# ESP32.net
KiCad netlist of a schematic drawn in EasyEDA Pro
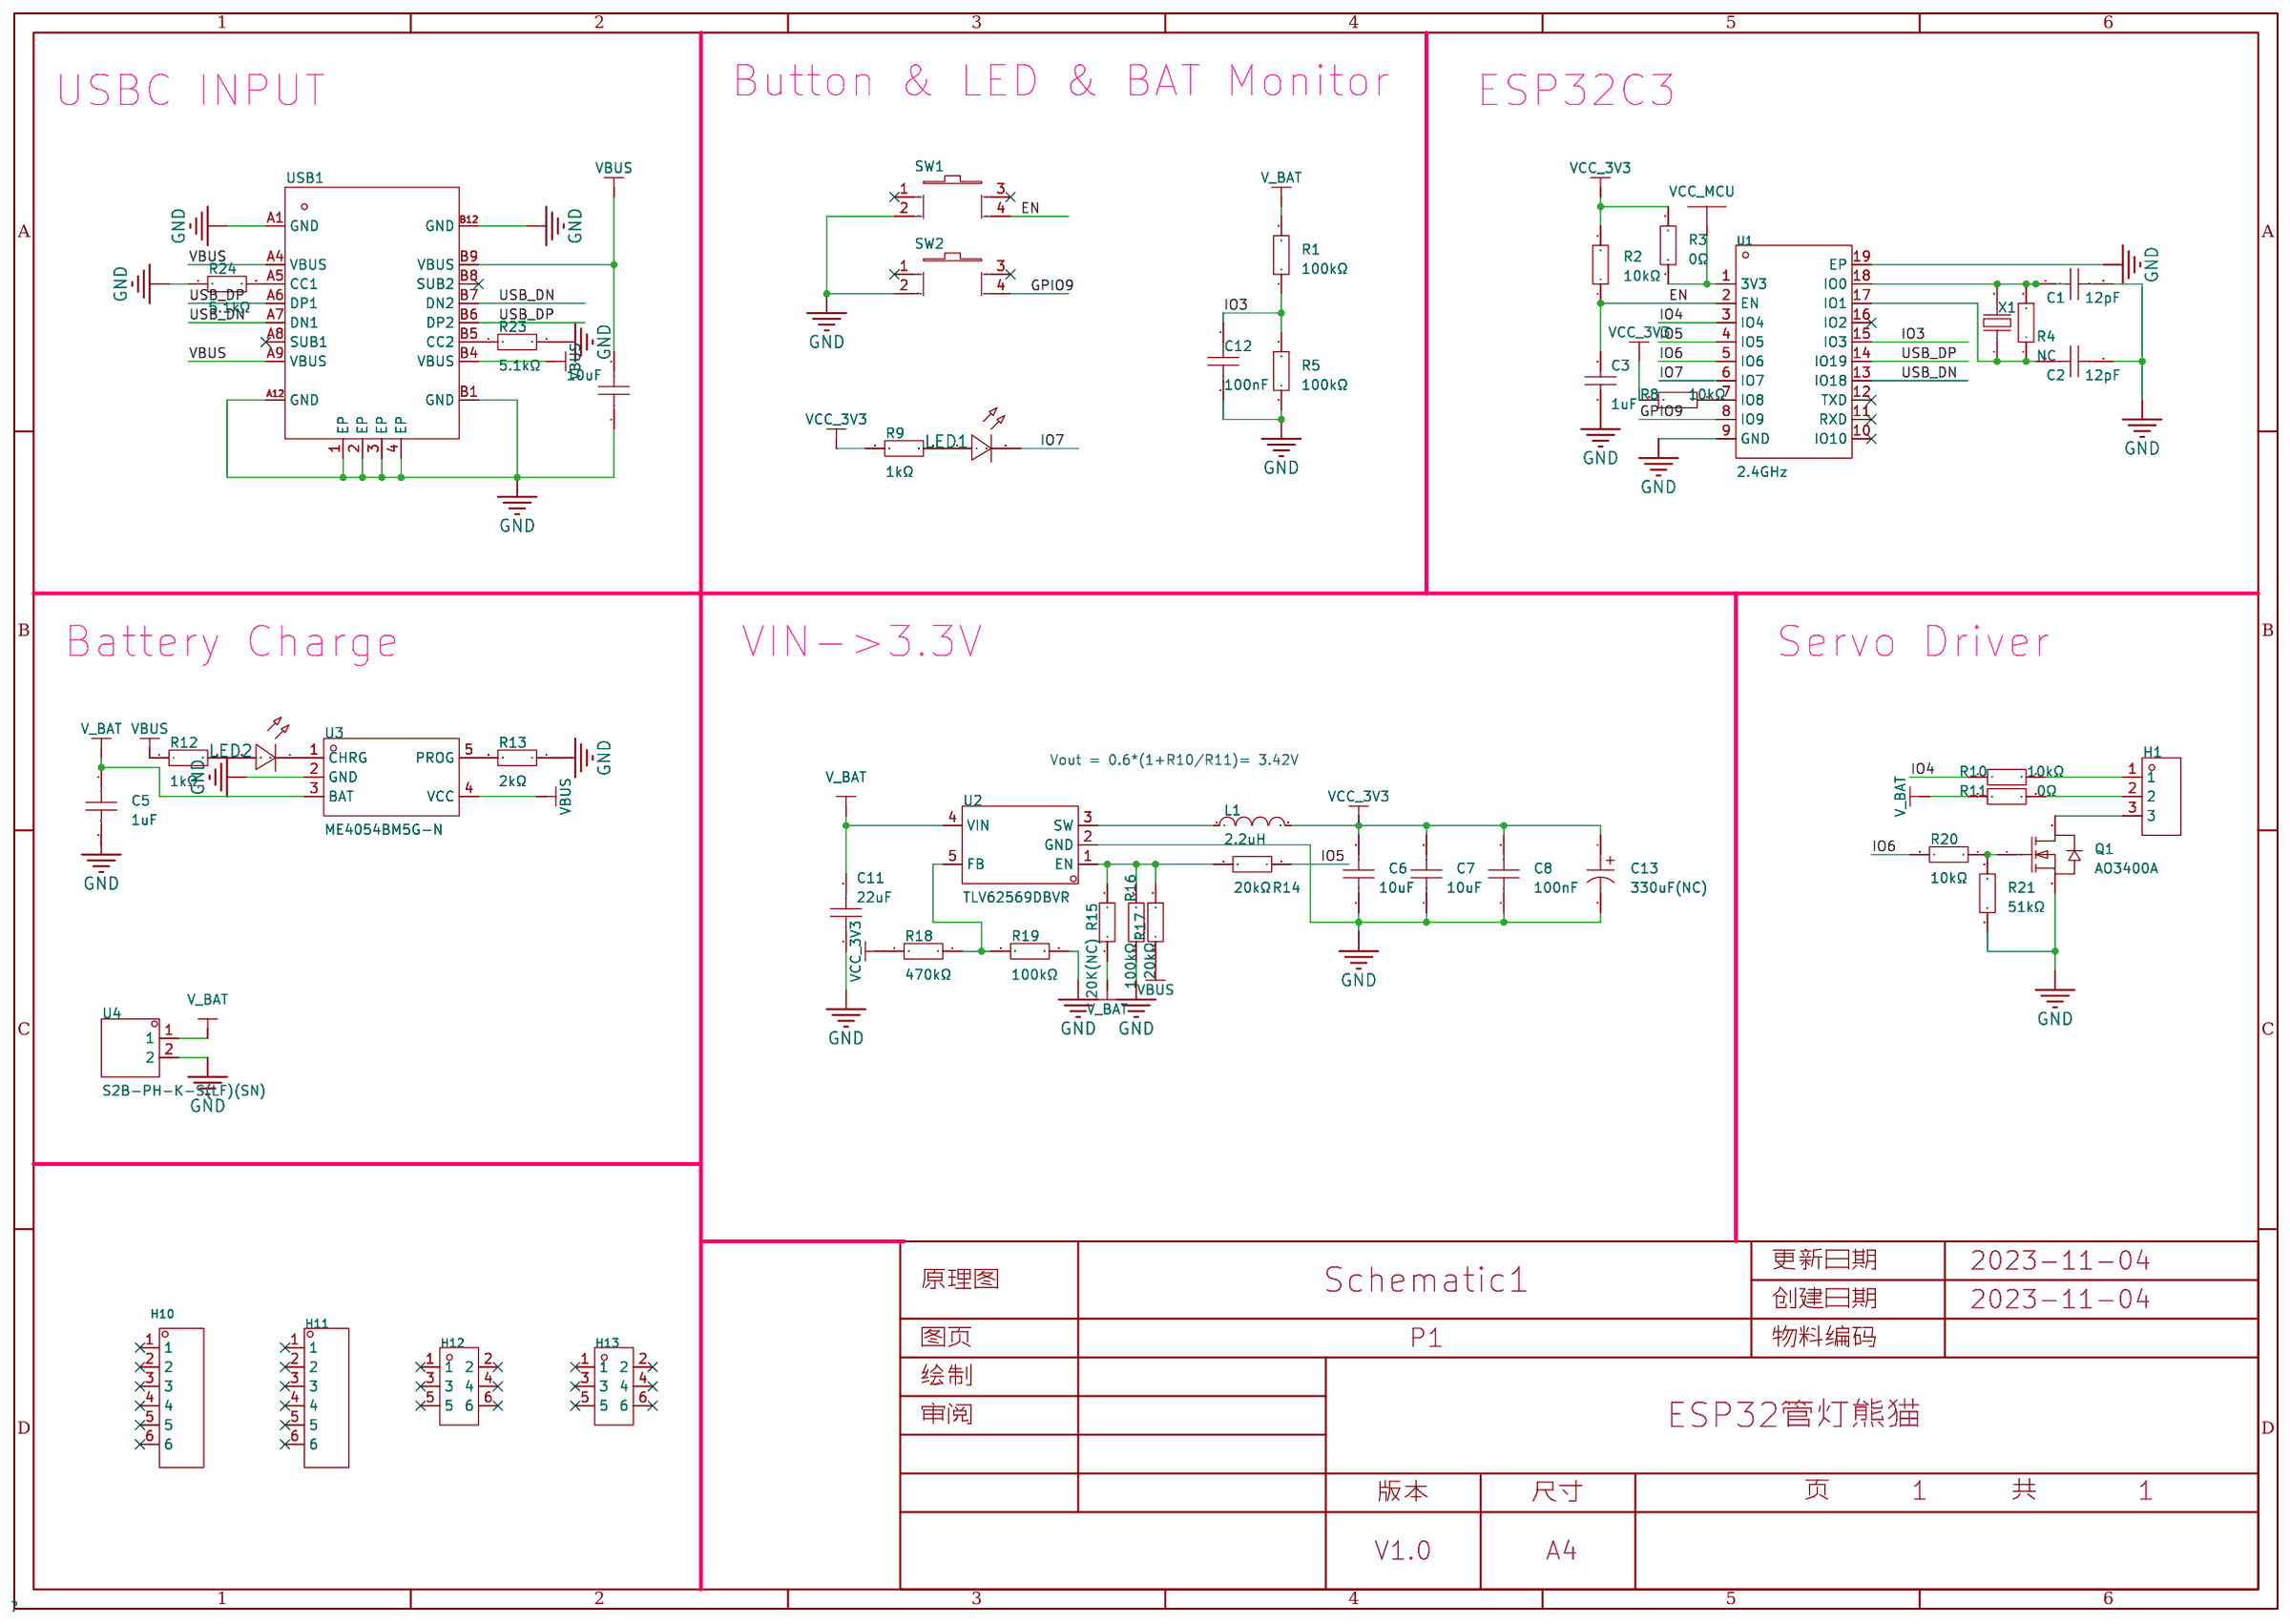
[diagram p0: schematic sheet]

(export (version "E")
  (design (tool "Eeschema 10.0.6"))
  (components
    (comp (ref "C1")
      (value "12pF")
      (footprint "easyedapro:C0603")
      (fields
        (field (name "Manufacturer Part") "CL10C120JB8NNNC")
        (field (name "Manufacturer") "SAMSUNG(三星)")
      )
      (libsource (lib "easyedapro") (part "CapAcitance"))
    )
    (comp (ref "C2")
      (value "12pF")
      (footprint "easyedapro:C0603")
      (fields
        (field (name "Manufacturer Part") "CL10C120JB8NNNC")
        (field (name "Manufacturer") "SAMSUNG(三星)")
      )
      (libsource (lib "easyedapro") (part "CapAcitance"))
    )
    (comp (ref "C3")
      (value "1uF")
      (footprint "easyedapro:C0603")
      (description "容值:1uF;精度:±10%;额定电压:25V;温度系数:X5R;")
      (fields
        (field (name "Manufacturer Part") "CL10A105KA8NNNC")
        (field (name "Manufacturer") "SAMSUNG(三星)")
      )
      (libsource (lib "easyedapro") (part "CL10A105KA8NNNC"))
    )
    (comp (ref "C4")
      (value "10uF")
      (footprint "easyedapro:C0603")
      (description "容值:10uF;精度:±20%;额定电压:10V;温度系数:X5R;")
      (fields
        (field (name "Manufacturer Part") "CL10A106MP8NNNC")
        (field (name "Manufacturer") "SAMSUNG(三星)")
      )
      (libsource (lib "easyedapro") (part "CL10A106MP8NNNC"))
    )
    (comp (ref "C5")
      (value "1uF")
      (footprint "easyedapro:C0603")
      (fields
        (field (name "Manufacturer Part") "CL10A105KB8NNNC")
        (field (name "Manufacturer") "SAMSUNG(三星)")
      )
      (libsource (lib "easyedapro") (part "CapAcitance"))
    )
    (comp (ref "C6")
      (value "10uF")
      (footprint "easyedapro:C0603")
      (fields
        (field (name "Manufacturer Part") "CL10A106KP8NNNC")
        (field (name "Manufacturer") "SAMSUNG(三星)")
      )
      (libsource (lib "easyedapro") (part "CapAcitance"))
    )
    (comp (ref "C7")
      (value "10uF")
      (footprint "easyedapro:C0603")
      (fields
        (field (name "Manufacturer Part") "CL10A106KP8NNNC")
        (field (name "Manufacturer") "SAMSUNG(三星)")
      )
      (libsource (lib "easyedapro") (part "CapAcitance"))
    )
    (comp (ref "C8")
      (value "100nF")
      (footprint "easyedapro:C0603")
      (fields
        (field (name "Manufacturer Part") "CC0603KRX7R9BB104")
        (field (name "Manufacturer") "YAGEO(国巨)")
      )
      (libsource (lib "easyedapro") (part "CapAcitance"))
    )
    (comp (ref "C11")
      (value "22uF")
      (footprint "easyedapro:C0603")
      (fields
        (field (name "Manufacturer Part") "CL10A226MQ8NRNC")
        (field (name "Manufacturer") "SAMSUNG(三星)")
      )
      (libsource (lib "easyedapro") (part "CapAcitance"))
    )
    (comp (ref "C12")
      (value "100nF")
      (footprint "easyedapro:C0603")
      (fields
        (field (name "Manufacturer Part") "CC0603KRX7R9BB104")
        (field (name "Manufacturer") "YAGEO(国巨)")
      )
      (libsource (lib "easyedapro") (part "CapAcitance"))
    )
    (comp (ref "C13")
      (value "330uF(NC)")
      (footprint "easyedapro:CAP-SMD_BD6.3-L6.6-W6.6-LS7.4-FD")
      (description "容值:330uF;精度:±20%;额定电压:6.3V;")
      (fields (field (name "Manufacturer Part") "RVT0J331M0605") (field (name "Manufacturer") "ROQANG(容强)"))
      (libsource (lib "easyedapro") (part "RVT0J331M0605"))
    )
    (comp (ref "H1")
      (value "~")
      (footprint "easyedapro:HDR-TH_3P-P2.54-V-M")
      (libsource (lib "easyedapro") (part "PZ254V-11-03P_C2937625"))
    )
    (comp (ref "H10")
      (value "B-2200S06P-A120")
      (footprint "easyedapro:HDR-TH_6P-P2.54-V-F")
      (description "排数:单排;总孔位数:6;间距:2.54mm;插孔结构:1x6P;行距:-;安装类型:直插;塑高:-;触头材质:黄铜;触头镀层:-;")
      (fields (field (name "Manufacturer") "Ckmtw(灿科盟)"))
      (libsource (lib "easyedapro") (part "220S-1*6P H=8.5MM Ytype Gold-plated"))
    )
    (comp (ref "H11")
      (value "B-2200S06P-A120")
      (footprint "easyedapro:HDR-TH_6P-P2.54-V-F")
      (description "排数:单排;总孔位数:6;间距:2.54mm;插孔结构:1x6P;行距:-;安装类型:直插;塑高:-;触头材质:黄铜;触头镀层:-;")
      (fields (field (name "Manufacturer") "Ckmtw(灿科盟)"))
      (libsource (lib "easyedapro") (part "220S-1*6P H=8.5MM Ytype Gold-plated"))
    )
    (comp (ref "H12")
      (value "X6511WVS-06H-C60D48R2")
      (footprint "easyedapro:HDR-SMD_6P-P2.54-V-M-LS4.8_R2")
      (fields (field (name "Manufacturer") "XKB Connectivity(中国星坤)"))
      (libsource (lib "easyedapro") (part "X6511WVS-06H-C60D48R2"))
    )
    (comp (ref "H13")
      (value "X6511WVS-06H-C60D48R2")
      (footprint "easyedapro:HDR-SMD_6P-P2.54-V-M-LS4.8_R2")
      (fields (field (name "Manufacturer") "XKB Connectivity(中国星坤)"))
      (libsource (lib "easyedapro") (part "X6511WVS-06H-C60D48R2"))
    )
    (comp (ref "L1")
      (value "2.2uH")
      (footprint "easyedapro:IND-SMD_L2.5-W2.0_SWPA2520")
      (description "电感值:2.2uH;精度:±20%;额定电流:1.25A;直流电阻(DCR):216mΩ;")
      (fields
        (field (name "Manufacturer Part") "SWPA252012S2R2MT")
        (field (name "Manufacturer") "Sunlord(顺络)")
      )
      (libsource (lib "easyedapro") (part "SWPA252012S-2R2MT"))
    )
    (comp (ref "LED1")
      (value "19-217/BHC-ZL1M2RY/3T")
      (description "发光颜色:蓝灯;二极管配置:-;主波长:465nm~475nm;色温:-;功率:110mW;安装方式:-;")
      (fields (field (name "Manufacturer") "EVERLIGHT(亿光)"))
      (libsource (lib "easyedapro") (part "LED_R"))
    )
    (comp (ref "LED2")
      (value "19-217/BHC-ZL1M2RY/3T")
      (description "发光颜色:蓝灯;二极管配置:-;主波长:465nm~475nm;色温:-;功率:110mW;安装方式:-;")
      (fields (field (name "Manufacturer") "EVERLIGHT(亿光)"))
      (libsource (lib "easyedapro") (part "LED_R"))
    )
    (comp (ref "Q1")
      (value "AO3400A")
      (footprint "easyedapro:SOT-23-3_L2.9-W1.6-P1.90-LS2.8-BR")
      (description "类型:N沟道;漏源电压(Vdss):30V;连续漏极电流(Id):5.7A;功率(Pd):1.4W;导通电阻(RDS(on)@Vgs,Id):26.5mΩ@10V,5.7A;")
      (fields (field (name "Manufacturer") "AOS"))
      (libsource (lib "easyedapro") (part "AO3400A"))
    )
    (comp (ref "R1")
      (value "100kΩ")
      (footprint "easyedapro:R0603")
      (fields
        (field (name "Manufacturer Part") "0603WAF1003T5E")
        (field (name "Manufacturer") "UNI-ROYAL(厚声)")
      )
      (libsource (lib "easyedapro") (part "电阻"))
    )
    (comp (ref "R2")
      (value "10kΩ")
      (footprint "easyedapro:R0402")
      (fields
        (field (name "Manufacturer Part") "0603WAF1002T5E")
        (field (name "Manufacturer") "UNI-ROYAL(厚声)")
      )
      (libsource (lib "easyedapro") (part "电阻"))
    )
    (comp (ref "R3")
      (value "0Ω")
      (footprint "easyedapro:R0603")
      (fields
        (field (name "Manufacturer Part") "0603WAF0000T5E")
        (field (name "Manufacturer") "UNI-ROYAL(厚声)")
      )
      (libsource (lib "easyedapro") (part "电阻"))
    )
    (comp (ref "R4") (value "NC") (footprint "easyedapro:R0603") (libsource (lib "easyedapro") (part "电阻")))
    (comp (ref "R5")
      (value "100kΩ")
      (footprint "easyedapro:R0603")
      (fields
        (field (name "Manufacturer Part") "0603WAF1003T5E")
        (field (name "Manufacturer") "UNI-ROYAL(厚声)")
      )
      (libsource (lib "easyedapro") (part "电阻"))
    )
    (comp (ref "R8")
      (value "10kΩ")
      (footprint "easyedapro:R0402")
      (fields
        (field (name "Manufacturer Part") "0603WAF1002T5E")
        (field (name "Manufacturer") "UNI-ROYAL(厚声)")
      )
      (libsource (lib "easyedapro") (part "电阻"))
    )
    (comp (ref "R9")
      (value "1kΩ")
      (footprint "easyedapro:R0402")
      (fields
        (field (name "Manufacturer Part") "0603WAF1001T5E")
        (field (name "Manufacturer") "UNI-ROYAL(厚声)")
      )
      (libsource (lib "easyedapro") (part "电阻"))
    )
    (comp (ref "R10")
      (value "10kΩ")
      (footprint "easyedapro:R0603")
      (fields
        (field (name "Manufacturer Part") "0603WAF1002T5E")
        (field (name "Manufacturer") "UNI-ROYAL(厚声)")
      )
      (libsource (lib "easyedapro") (part "电阻"))
    )
    (comp (ref "R11")
      (value "0Ω")
      (footprint "easyedapro:R0603")
      (fields
        (field (name "Manufacturer Part") "0603WAF0000T5E")
        (field (name "Manufacturer") "UNI-ROYAL(厚声)")
      )
      (libsource (lib "easyedapro") (part "电阻"))
    )
    (comp (ref "R12")
      (value "1kΩ")
      (footprint "easyedapro:R0402")
      (fields
        (field (name "Manufacturer Part") "0603WAF1001T5E")
        (field (name "Manufacturer") "UNI-ROYAL(厚声)")
      )
      (libsource (lib "easyedapro") (part "电阻"))
    )
    (comp (ref "R13")
      (value "2kΩ")
      (footprint "easyedapro:R0402")
      (fields
        (field (name "Manufacturer Part") "0603WAF2001T5E")
        (field (name "Manufacturer") "UNI-ROYAL(厚声)")
      )
      (libsource (lib "easyedapro") (part "电阻"))
    )
    (comp (ref "R14")
      (value "20kΩ")
      (footprint "easyedapro:R0402")
      (fields
        (field (name "Manufacturer Part") "0603WAF2002T5E")
        (field (name "Manufacturer") "UNI-ROYAL(厚声)")
      )
      (libsource (lib "easyedapro") (part "电阻"))
    )
    (comp (ref "R15")
      (value "20K(NC)")
      (footprint "easyedapro:R0402")
      (libsource (lib "easyedapro") (part "电阻"))
    )
    (comp (ref "R16")
      (value "100kΩ")
      (footprint "easyedapro:R0402")
      (fields
        (field (name "Manufacturer Part") "0603WAF1003T5E")
        (field (name "Manufacturer") "UNI-ROYAL(厚声)")
      )
      (libsource (lib "easyedapro") (part "电阻"))
    )
    (comp (ref "R17")
      (value "20kΩ")
      (footprint "easyedapro:R0402")
      (fields
        (field (name "Manufacturer Part") "0603WAF2002T5E")
        (field (name "Manufacturer") "UNI-ROYAL(厚声)")
      )
      (libsource (lib "easyedapro") (part "电阻"))
    )
    (comp (ref "R18")
      (value "470kΩ")
      (footprint "easyedapro:R0402")
      (fields
        (field (name "Manufacturer Part") "0603WAF4703T5E")
        (field (name "Manufacturer") "UNI-ROYAL(厚声)")
      )
      (libsource (lib "easyedapro") (part "电阻"))
    )
    (comp (ref "R19")
      (value "100kΩ")
      (footprint "easyedapro:R0402")
      (fields
        (field (name "Manufacturer Part") "0603WAF1003T5E")
        (field (name "Manufacturer") "UNI-ROYAL(厚声)")
      )
      (libsource (lib "easyedapro") (part "电阻"))
    )
    (comp (ref "R20")
      (value "10kΩ")
      (footprint "easyedapro:R0402")
      (fields
        (field (name "Manufacturer Part") "0603WAF1002T5E")
        (field (name "Manufacturer") "UNI-ROYAL(厚声)")
      )
      (libsource (lib "easyedapro") (part "电阻"))
    )
    (comp (ref "R21")
      (value "51kΩ")
      (footprint "easyedapro:R0402")
      (fields
        (field (name "Manufacturer Part") "0603WAF5102T5E")
        (field (name "Manufacturer") "UNI-ROYAL(厚声)")
      )
      (libsource (lib "easyedapro") (part "电阻"))
    )
    (comp (ref "R23")
      (value "5.1kΩ")
      (footprint "easyedapro:R0603")
      (description "电阻类型:厚膜电阻;阻值:5.1kΩ;精度:±1%;功率:100mW;")
      (fields
        (field (name "Manufacturer Part") "0603WAF5101T5E")
        (field (name "Manufacturer") "UNI-ROYAL(厚声)")
      )
      (libsource (lib "easyedapro") (part "0603WAF5101T5E"))
    )
    (comp (ref "R24")
      (value "5.1kΩ")
      (footprint "easyedapro:R0603")
      (description "电阻类型:厚膜电阻;阻值:5.1kΩ;精度:±1%;功率:100mW;")
      (fields
        (field (name "Manufacturer Part") "0603WAF5101T5E")
        (field (name "Manufacturer") "UNI-ROYAL(厚声)")
      )
      (libsource (lib "easyedapro") (part "0603WAF5101T5E"))
    )
    (comp (ref "SW1")
      (value "~")
      (footprint "easyedapro:SW-SMD_4P_PTS810SJM250SMTRLFS")
      (description "触点电流:50mA;额定电压(DC):16V;电路结构:单刀单掷;安装方式:-;按钮形状:圆形按钮;带灯:-;开关长度:4.2mm;开关宽度:3.2mm;开关高度:2.5mm;")
      (fields
        (field (name "Manufacturer Part") "PTS810SJS250SMTRLFS")
        (field (name "Manufacturer") "C&amp;K")
      )
      (libsource (lib "easyedapro") (part "PTS810SJS250SMTRLFS"))
    )
    (comp (ref "SW2")
      (value "~")
      (footprint "easyedapro:SW-SMD_4P_PTS810SJM250SMTRLFS")
      (description "触点电流:50mA;额定电压(DC):16V;电路结构:单刀单掷;安装方式:-;按钮形状:圆形按钮;带灯:-;开关长度:4.2mm;开关宽度:3.2mm;开关高度:2.5mm;")
      (fields
        (field (name "Manufacturer Part") "PTS810SJS250SMTRLFS")
        (field (name "Manufacturer") "C&amp;K")
      )
      (libsource (lib "easyedapro") (part "PTS810SJS250SMTRLFS"))
    )
    (comp (ref "U1")
      (value "2.4GHz")
      (footprint "easyedapro:BULETM-SMD_ESPRESSIF_ESP32-C3-WROOM-02-N4-4MB")
      (description "频率:2.4GHz;发射功率:20.5dBm;核心处理器:ESP32-C3;")
      (fields
        (field (name "Manufacturer Part") "ESP32-C3-WROOM-02-N4")
        (field (name "Manufacturer") "ESPRESSIF(乐鑫)")
      )
      (libsource (lib "easyedapro") (part "ESP32-C3-WROOM-02-N4(4MB)"))
    )
    (comp (ref "U2")
      (value "TLV62569DBVR")
      (footprint "easyedapro:SOT-23-5_L3.0-W1.7-P0.95-LS2.8-BR")
      (description "功能类型:降压型;输出类型:可调;输入电压:2.5V~5.5V;输出电压:600mV~5.5V;输出电流(最大值):2A;")
      (fields (field (name "Manufacturer") "TI(德州仪器)"))
      (libsource (lib "easyedapro") (part "TLV62569DBVR"))
    )
    (comp (ref "U3")
      (value "ME4054BM5G-N")
      (footprint "easyedapro:TSOT-23-5_L2.9-W1.6-P0.95-LS2.8-BL")
      (fields (field (name "Manufacturer") "MICRONE(南京微盟)"))
      (libsource (lib "easyedapro") (part "ME4054BM5G-N"))
    )
    (comp (ref "U4")
      (value "S2B-PH-K-S(LF)(SN)")
      (footprint "easyedapro:CONN-TH_S2B-PH-K-S-LF-SN")
      (description "参考系列:PH;间距:2mm;插针结构:1x2P;排数:1;每排PIN数:2;行距:-;安装方式:-;触头材质:黄铜;")
      (fields (field (name "Manufacturer") "JST"))
      (libsource (lib "easyedapro") (part "S2B-PH-K-S(LF)(SN)"))
    )
    (comp (ref "USB1")
      (value "KH-TYPE-C-16P")
      (fields (field (name "Manufacturer") "kinghelm(金航标)"))
      (libsource (lib "easyedapro") (part "KH-TYPE-C-16P"))
    )
    (comp (ref "X1")
      (value "32.768kHz")
      (footprint "easyedapro:FC-135R_L3.2-W1.5")
      (description "频率:32.768kHz;频率公差:±20ppm;负载电容:12.5pF;")
      (fields (field (name "Manufacturer Part") "Q13FC1350000400") (field (name "Manufacturer") "EPSON(爱普生)"))
      (libsource (lib "easyedapro") (part "Q13FC1350000400"))
    )
  )
  (nets
    (net (code "1") (name "/EN") (class "Default")
      (node (ref "C3") (pin "2") (pinfunction "2_2") (pintype "input"))
      (node (ref "R2") (pin "1") (pinfunction "1_1") (pintype "input"))
      (node (ref "SW1") (pin "4") (pinfunction "4_4") (pintype "input"))
      (node (ref "U1") (pin "2") (pinfunction "EN_2") (pintype "input"))
    )
    (net (code "2") (name "/GPIO9") (class "Default")
      (node (ref "SW2") (pin "4") (pinfunction "4_4") (pintype "input"))
      (node (ref "U1") (pin "8") (pinfunction "IO9_8") (pintype "input"))
    )
    (net (code "3") (name "/IO3") (class "Default")
      (node (ref "C12") (pin "2") (pinfunction "2_2") (pintype "input"))
      (node (ref "R1") (pin "1") (pinfunction "1_1") (pintype "input"))
      (node (ref "R5") (pin "2") (pinfunction "2_2") (pintype "input"))
      (node (ref "U1") (pin "15") (pinfunction "IO3_15") (pintype "input"))
    )
    (net (code "4") (name "/IO4") (class "Default")
      (node (ref "R10") (pin "1") (pinfunction "1_1") (pintype "input"))
      (node (ref "U1") (pin "3") (pinfunction "IO4_3") (pintype "input"))
    )
    (net (code "5") (name "/IO5") (class "Default")
      (node (ref "R14") (pin "1") (pinfunction "1_1") (pintype "input"))
      (node (ref "U1") (pin "4") (pinfunction "IO5_4") (pintype "input"))
    )
    (net (code "6") (name "/IO6") (class "Default")
      (node (ref "R20") (pin "2") (pinfunction "2_2") (pintype "input"))
      (node (ref "U1") (pin "5") (pinfunction "IO6_5") (pintype "input"))
    )
    (net (code "7") (name "/IO7") (class "Default")
      (node (ref "LED1") (pin "1") (pinfunction "C_1") (pintype "input"))
      (node (ref "U1") (pin "6") (pinfunction "IO7_6") (pintype "input"))
    )
    (net (code "8") (name "/USB_DN") (class "Default")
      (node (ref "U1") (pin "13") (pinfunction "IO18_13") (pintype "input"))
      (node (ref "USB1") (pin "A7") (pinfunction "DN1_A7") (pintype "input"))
      (node (ref "USB1") (pin "B7") (pinfunction "DN2_B7") (pintype "input"))
    )
    (net (code "9") (name "/USB_DP") (class "Default")
      (node (ref "U1") (pin "14") (pinfunction "IO19_14") (pintype "input"))
      (node (ref "USB1") (pin "A6") (pinfunction "DP1_A6") (pintype "input"))
      (node (ref "USB1") (pin "B6") (pinfunction "DP2_B6") (pintype "input"))
    )
    (net (code "10") (name "GND") (class "Default")
      (node (ref "C1") (pin "2") (pinfunction "2_2") (pintype "input"))
      (node (ref "C11") (pin "1") (pinfunction "1_1") (pintype "input"))
      (node (ref "C12") (pin "1") (pinfunction "1_1") (pintype "input"))
      (node (ref "C13") (pin "2") (pinfunction "2_2") (pintype "input"))
      (node (ref "C2") (pin "2") (pinfunction "2_2") (pintype "input"))
      (node (ref "C3") (pin "1") (pinfunction "1_1") (pintype "input"))
      (node (ref "C4") (pin "1") (pinfunction "1_1") (pintype "input"))
      (node (ref "C5") (pin "2") (pinfunction "2_2") (pintype "input"))
      (node (ref "C6") (pin "1") (pinfunction "1_1") (pintype "input"))
      (node (ref "C7") (pin "1") (pinfunction "1_1") (pintype "input"))
      (node (ref "C8") (pin "1") (pinfunction "1_1") (pintype "input"))
      (node (ref "Q1") (pin "2") (pinfunction "S_2") (pintype "input"))
      (node (ref "R13") (pin "1") (pinfunction "1_1") (pintype "input"))
      (node (ref "R16") (pin "1") (pinfunction "1_1") (pintype "input"))
      (node (ref "R19") (pin "1") (pinfunction "1_1") (pintype "input"))
      (node (ref "R21") (pin "1") (pinfunction "1_1") (pintype "input"))
      (node (ref "R23") (pin "2") (pinfunction "2_2") (pintype "input"))
      (node (ref "R24") (pin "1") (pinfunction "1_1") (pintype "input"))
      (node (ref "R5") (pin "1") (pinfunction "1_1") (pintype "input"))
      (node (ref "SW1") (pin "2") (pinfunction "2_2") (pintype "input"))
      (node (ref "SW2") (pin "2") (pinfunction "2_2") (pintype "input"))
      (node (ref "U1") (pin "19") (pinfunction "EP_19") (pintype "input"))
      (node (ref "U1") (pin "9") (pinfunction "GND_9") (pintype "input"))
      (node (ref "U2") (pin "2") (pinfunction "GND_2") (pintype "input"))
      (node (ref "U3") (pin "2") (pinfunction "GND_2") (pintype "input"))
      (node (ref "U4") (pin "2") (pinfunction "2_2") (pintype "input"))
      (node (ref "USB1") (pin "1") (pinfunction "EP_1") (pintype "input"))
      (node (ref "USB1") (pin "2") (pinfunction "EP_2") (pintype "input"))
      (node (ref "USB1") (pin "3") (pinfunction "EP_3") (pintype "input"))
      (node (ref "USB1") (pin "4") (pinfunction "EP_4") (pintype "input"))
      (node (ref "USB1") (pin "A1") (pinfunction "GND_A1") (pintype "input"))
      (node (ref "USB1") (pin "A12") (pinfunction "GND_A12") (pintype "input"))
      (node (ref "USB1") (pin "B1") (pinfunction "GND_B1") (pintype "input"))
      (node (ref "USB1") (pin "B12") (pinfunction "GND_B12") (pintype "input"))
    )
    (net (code "11") (name "Net-(H1-Pad1)") (class "Default")
      (node (ref "H1") (pin "1") (pinfunction "1_1") (pintype "input"))
      (node (ref "R10") (pin "2") (pinfunction "2_2") (pintype "input"))
    )
    (net (code "12") (name "Net-(H1-Pad2)") (class "Default")
      (node (ref "H1") (pin "2") (pinfunction "2_2") (pintype "input"))
      (node (ref "R11") (pin "2") (pinfunction "2_2") (pintype "input"))
    )
    (net (code "13") (name "Net-(LED1-A)") (class "Default")
      (node (ref "LED1") (pin "2") (pinfunction "A_2") (pintype "input"))
      (node (ref "R9") (pin "2") (pinfunction "2_2") (pintype "input"))
    )
    (net (code "14") (name "Net-(LED2-A)") (class "Default")
      (node (ref "LED2") (pin "2") (pinfunction "A_2") (pintype "input"))
      (node (ref "R12") (pin "2") (pinfunction "2_2") (pintype "input"))
    )
    (net (code "15") (name "Net-(LED2-C)") (class "Default")
      (node (ref "LED2") (pin "1") (pinfunction "C_1") (pintype "input"))
      (node (ref "U3") (pin "1") (pinfunction "CHRG_1") (pintype "input"))
    )
    (net (code "16") (name "Net-(Q1-D)") (class "Default")
      (node (ref "H1") (pin "3") (pinfunction "3_3") (pintype "input"))
      (node (ref "Q1") (pin "3") (pinfunction "D_3") (pintype "input"))
    )
    (net (code "17") (name "Net-(Q1-G)") (class "Default")
      (node (ref "Q1") (pin "1") (pinfunction "G_1") (pintype "input"))
      (node (ref "R20") (pin "1") (pinfunction "1_1") (pintype "input"))
      (node (ref "R21") (pin "2") (pinfunction "2_2") (pintype "input"))
    )
    (net (code "18") (name "Net-(U1-IO0)") (class "Default")
      (node (ref "C1") (pin "1") (pinfunction "1_1") (pintype "input"))
      (node (ref "R4") (pin "2") (pinfunction "2_2") (pintype "input"))
      (node (ref "U1") (pin "18") (pinfunction "IO0_18") (pintype "input"))
      (node (ref "X1") (pin "2") (pinfunction "2_2") (pintype "input"))
    )
    (net (code "19") (name "Net-(U1-IO1)") (class "Default")
      (node (ref "C2") (pin "1") (pinfunction "1_1") (pintype "input"))
      (node (ref "R4") (pin "1") (pinfunction "1_1") (pintype "input"))
      (node (ref "U1") (pin "17") (pinfunction "IO1_17") (pintype "input"))
      (node (ref "X1") (pin "1") (pinfunction "1_1") (pintype "input"))
    )
    (net (code "20") (name "Net-(U1-IO8)") (class "Default")
      (node (ref "R8") (pin "1") (pinfunction "1_1") (pintype "input"))
      (node (ref "U1") (pin "7") (pinfunction "IO8_7") (pintype "input"))
    )
    (net (code "21") (name "Net-(U2-EN)") (class "Default")
      (node (ref "R14") (pin "2") (pinfunction "2_2") (pintype "input"))
      (node (ref "R15") (pin "2") (pinfunction "2_2") (pintype "input"))
      (node (ref "R16") (pin "2") (pinfunction "2_2") (pintype "input"))
      (node (ref "R17") (pin "2") (pinfunction "2_2") (pintype "input"))
      (node (ref "U2") (pin "1") (pinfunction "EN_1") (pintype "input"))
    )
    (net (code "22") (name "Net-(U2-FB)") (class "Default")
      (node (ref "R18") (pin "1") (pinfunction "1_1") (pintype "input"))
      (node (ref "R19") (pin "2") (pinfunction "2_2") (pintype "input"))
      (node (ref "U2") (pin "5") (pinfunction "FB_5") (pintype "input"))
    )
    (net (code "23") (name "Net-(U2-SW)") (class "Default")
      (node (ref "L1") (pin "1") (pinfunction "1_1") (pintype "input"))
      (node (ref "U2") (pin "3") (pinfunction "SW_3") (pintype "input"))
    )
    (net (code "24") (name "Net-(U3-PROG)") (class "Default")
      (node (ref "R13") (pin "2") (pinfunction "2_2") (pintype "input"))
      (node (ref "U3") (pin "5") (pinfunction "PROG_5") (pintype "input"))
    )
    (net (code "25") (name "Net-(USB1-CC1)") (class "Default")
      (node (ref "R24") (pin "2") (pinfunction "2_2") (pintype "input"))
      (node (ref "USB1") (pin "A5") (pinfunction "CC1_A5") (pintype "input"))
    )
    (net (code "26") (name "Net-(USB1-CC2)") (class "Default")
      (node (ref "R23") (pin "1") (pinfunction "1_1") (pintype "input"))
      (node (ref "USB1") (pin "B5") (pinfunction "CC2_B5") (pintype "input"))
    )
    (net (code "27") (name "VBUS") (class "Default")
      (node (ref "C4") (pin "2") (pinfunction "2_2") (pintype "input"))
      (node (ref "R12") (pin "1") (pinfunction "1_1") (pintype "input"))
      (node (ref "R17") (pin "1") (pinfunction "1_1") (pintype "input"))
      (node (ref "U3") (pin "4") (pinfunction "VCC_4") (pintype "input"))
      (node (ref "USB1") (pin "A4") (pinfunction "VBUS_A4") (pintype "input"))
      (node (ref "USB1") (pin "A9") (pinfunction "VBUS_A9") (pintype "input"))
      (node (ref "USB1") (pin "B4") (pinfunction "VBUS_B4") (pintype "input"))
      (node (ref "USB1") (pin "B9") (pinfunction "VBUS_B9") (pintype "input"))
    )
    (net (code "28") (name "VCC_3V3") (class "Default")
      (node (ref "C13") (pin "1") (pinfunction "1_1") (pintype "input"))
      (node (ref "C6") (pin "2") (pinfunction "2_2") (pintype "input"))
      (node (ref "C7") (pin "2") (pinfunction "2_2") (pintype "input"))
      (node (ref "C8") (pin "2") (pinfunction "2_2") (pintype "input"))
      (node (ref "L1") (pin "2") (pinfunction "2_2") (pintype "input"))
      (node (ref "R18") (pin "2") (pinfunction "2_2") (pintype "input"))
      (node (ref "R2") (pin "2") (pinfunction "2_2") (pintype "input"))
      (node (ref "R3") (pin "2") (pinfunction "2_2") (pintype "input"))
      (node (ref "R8") (pin "2") (pinfunction "2_2") (pintype "input"))
      (node (ref "R9") (pin "1") (pinfunction "1_1") (pintype "input"))
    )
    (net (code "29") (name "VCC_MCU") (class "Default")
      (node (ref "R3") (pin "1") (pinfunction "1_1") (pintype "input"))
      (node (ref "U1") (pin "1") (pinfunction "3V3_1") (pintype "input"))
    )
    (net (code "30") (name "V_BAT") (class "Default")
      (node (ref "C11") (pin "2") (pinfunction "2_2") (pintype "input"))
      (node (ref "C5") (pin "1") (pinfunction "1_1") (pintype "input"))
      (node (ref "R1") (pin "2") (pinfunction "2_2") (pintype "input"))
      (node (ref "R11") (pin "1") (pinfunction "1_1") (pintype "input"))
      (node (ref "R15") (pin "1") (pinfunction "1_1") (pintype "input"))
      (node (ref "U2") (pin "4") (pinfunction "VIN_4") (pintype "input"))
      (node (ref "U3") (pin "3") (pinfunction "BAT_3") (pintype "input"))
      (node (ref "U4") (pin "1") (pinfunction "1_1") (pintype "input"))
    )
    (net (code "31") (name "unconnected-(H10-Pad1)") (class "Default")
      (node (ref "H10") (pin "1") (pinfunction "1_1") (pintype "input+no_connect"))
    )
    (net (code "32") (name "unconnected-(H10-Pad2)") (class "Default")
      (node (ref "H10") (pin "2") (pinfunction "2_2") (pintype "input+no_connect"))
    )
    (net (code "33") (name "unconnected-(H10-Pad3)") (class "Default")
      (node (ref "H10") (pin "3") (pinfunction "3_3") (pintype "input+no_connect"))
    )
    (net (code "34") (name "unconnected-(H10-Pad4)") (class "Default")
      (node (ref "H10") (pin "4") (pinfunction "4_4") (pintype "input+no_connect"))
    )
    (net (code "35") (name "unconnected-(H10-Pad5)") (class "Default")
      (node (ref "H10") (pin "5") (pinfunction "5_5") (pintype "input+no_connect"))
    )
    (net (code "36") (name "unconnected-(H10-Pad6)") (class "Default")
      (node (ref "H10") (pin "6") (pinfunction "6_6") (pintype "input+no_connect"))
    )
    (net (code "37") (name "unconnected-(H11-Pad1)") (class "Default")
      (node (ref "H11") (pin "1") (pinfunction "1_1") (pintype "input+no_connect"))
    )
    (net (code "38") (name "unconnected-(H11-Pad2)") (class "Default")
      (node (ref "H11") (pin "2") (pinfunction "2_2") (pintype "input+no_connect"))
    )
    (net (code "39") (name "unconnected-(H11-Pad3)") (class "Default")
      (node (ref "H11") (pin "3") (pinfunction "3_3") (pintype "input+no_connect"))
    )
    (net (code "40") (name "unconnected-(H11-Pad4)") (class "Default")
      (node (ref "H11") (pin "4") (pinfunction "4_4") (pintype "input+no_connect"))
    )
    (net (code "41") (name "unconnected-(H11-Pad5)") (class "Default")
      (node (ref "H11") (pin "5") (pinfunction "5_5") (pintype "input+no_connect"))
    )
    (net (code "42") (name "unconnected-(H11-Pad6)") (class "Default")
      (node (ref "H11") (pin "6") (pinfunction "6_6") (pintype "input+no_connect"))
    )
    (net (code "43") (name "unconnected-(H12-Pad1)") (class "Default")
      (node (ref "H12") (pin "1") (pinfunction "1_1") (pintype "input+no_connect"))
    )
    (net (code "44") (name "unconnected-(H12-Pad2)") (class "Default")
      (node (ref "H12") (pin "2") (pinfunction "2_2") (pintype "input+no_connect"))
    )
    (net (code "45") (name "unconnected-(H12-Pad3)") (class "Default")
      (node (ref "H12") (pin "3") (pinfunction "3_3") (pintype "input+no_connect"))
    )
    (net (code "46") (name "unconnected-(H12-Pad4)") (class "Default")
      (node (ref "H12") (pin "4") (pinfunction "4_4") (pintype "input+no_connect"))
    )
    (net (code "47") (name "unconnected-(H12-Pad5)") (class "Default")
      (node (ref "H12") (pin "5") (pinfunction "5_5") (pintype "input+no_connect"))
    )
    (net (code "48") (name "unconnected-(H12-Pad6)") (class "Default")
      (node (ref "H12") (pin "6") (pinfunction "6_6") (pintype "input+no_connect"))
    )
    (net (code "49") (name "unconnected-(H13-Pad1)") (class "Default")
      (node (ref "H13") (pin "1") (pinfunction "1_1") (pintype "input+no_connect"))
    )
    (net (code "50") (name "unconnected-(H13-Pad2)") (class "Default")
      (node (ref "H13") (pin "2") (pinfunction "2_2") (pintype "input+no_connect"))
    )
    (net (code "51") (name "unconnected-(H13-Pad3)") (class "Default")
      (node (ref "H13") (pin "3") (pinfunction "3_3") (pintype "input+no_connect"))
    )
    (net (code "52") (name "unconnected-(H13-Pad4)") (class "Default")
      (node (ref "H13") (pin "4") (pinfunction "4_4") (pintype "input+no_connect"))
    )
    (net (code "53") (name "unconnected-(H13-Pad5)") (class "Default")
      (node (ref "H13") (pin "5") (pinfunction "5_5") (pintype "input+no_connect"))
    )
    (net (code "54") (name "unconnected-(H13-Pad6)") (class "Default")
      (node (ref "H13") (pin "6") (pinfunction "6_6") (pintype "input+no_connect"))
    )
    (net (code "55") (name "unconnected-(SW1-Pad1)") (class "Default")
      (node (ref "SW1") (pin "1") (pinfunction "1_1") (pintype "input+no_connect"))
    )
    (net (code "56") (name "unconnected-(SW1-Pad3)") (class "Default")
      (node (ref "SW1") (pin "3") (pinfunction "3_3") (pintype "input+no_connect"))
    )
    (net (code "57") (name "unconnected-(SW2-Pad1)") (class "Default")
      (node (ref "SW2") (pin "1") (pinfunction "1_1") (pintype "input+no_connect"))
    )
    (net (code "58") (name "unconnected-(SW2-Pad3)") (class "Default")
      (node (ref "SW2") (pin "3") (pinfunction "3_3") (pintype "input+no_connect"))
    )
    (net (code "59") (name "unconnected-(U1-IO2-Pad16)") (class "Default")
      (node (ref "U1") (pin "16") (pinfunction "IO2_16") (pintype "input+no_connect"))
    )
    (net (code "60") (name "unconnected-(U1-IO10-Pad10)") (class "Default")
      (node (ref "U1") (pin "10") (pinfunction "IO10_10") (pintype "input+no_connect"))
    )
    (net (code "61") (name "unconnected-(U1-RXD-Pad11)") (class "Default")
      (node (ref "U1") (pin "11") (pinfunction "RXD_11") (pintype "input+no_connect"))
    )
    (net (code "62") (name "unconnected-(U1-TXD-Pad12)") (class "Default")
      (node (ref "U1") (pin "12") (pinfunction "TXD_12") (pintype "input+no_connect"))
    )
    (net (code "63") (name "unconnected-(USB1-SUB1-PadA8)") (class "Default")
      (node (ref "USB1") (pin "A8") (pinfunction "SUB1_A8") (pintype "input+no_connect"))
    )
    (net (code "64") (name "unconnected-(USB1-SUB2-PadB8)") (class "Default")
      (node (ref "USB1") (pin "B8") (pinfunction "SUB2_B8") (pintype "input+no_connect"))
    )
  )
)
